# TTGO_shield_revD.net
KiCad netlist of a schematic drawn in EAGLE
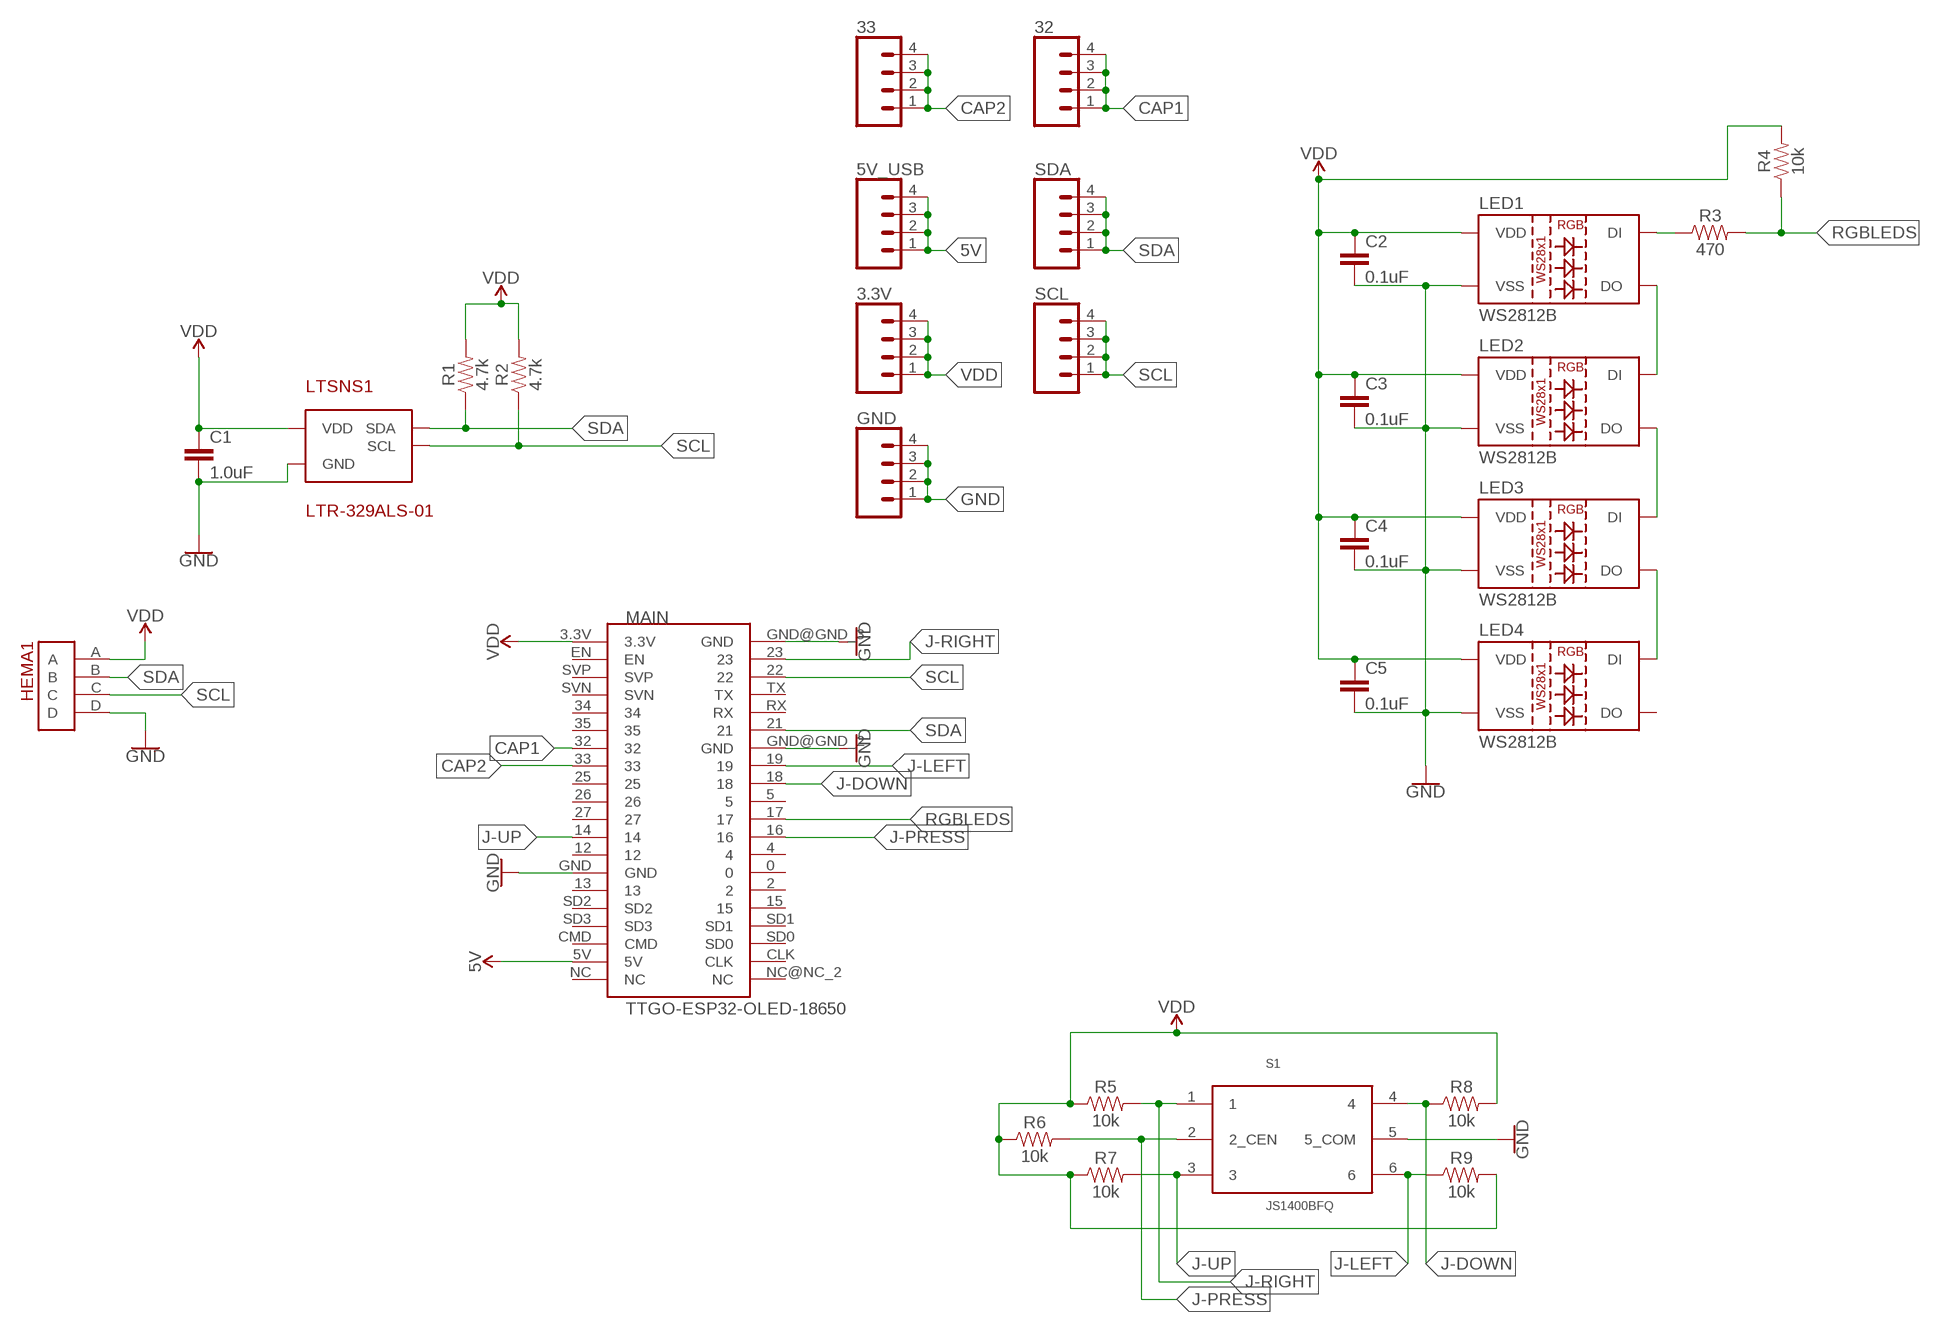
[diagram p0: schematic, sheet 1]

(export (version "E")
  (design (tool "Eeschema 10.0.6"))
  (components
    (comp (ref "3.3V")
      (value "CONN_041X04_NO_SILK")
      (footprint "eagle-import:1X04_NO_SILK")
      (libsource (lib "eagle-import") (part "CONN_041X04_NO_SILK"))
    )
    (comp (ref "5V_USB")
      (value "CONN_041X04_NO_SILK")
      (footprint "eagle-import:1X04_NO_SILK")
      (libsource (lib "eagle-import") (part "CONN_041X04_NO_SILK"))
    )
    (comp (ref "32")
      (value "CONN_041X04_NO_SILK")
      (footprint "eagle-import:1X04_NO_SILK")
      (libsource (lib "eagle-import") (part "CONN_041X04_NO_SILK"))
    )
    (comp (ref "33")
      (value "CONN_041X04_NO_SILK")
      (footprint "eagle-import:1X04_NO_SILK")
      (libsource (lib "eagle-import") (part "CONN_041X04_NO_SILK"))
    )
    (comp (ref "C1")
      (value "1.0uF")
      (footprint "eagle-import:0805")
      (libsource (lib "eagle-import") (part "1.0UF-0805-25V-10%"))
    )
    (comp (ref "C2")
      (value "0.1uF")
      (footprint "eagle-import:0603")
      (libsource (lib "eagle-import") (part "0.1UF-0603-25V-5%"))
    )
    (comp (ref "C3")
      (value "0.1uF")
      (footprint "eagle-import:0603")
      (libsource (lib "eagle-import") (part "0.1UF-0603-25V-5%"))
    )
    (comp (ref "C4")
      (value "0.1uF")
      (footprint "eagle-import:0603")
      (libsource (lib "eagle-import") (part "0.1UF-0603-25V-5%"))
    )
    (comp (ref "C5")
      (value "0.1uF")
      (footprint "eagle-import:0603")
      (libsource (lib "eagle-import") (part "0.1UF-0603-25V-5%"))
    )
    (comp (ref "GND")
      (value "CONN_041X04_NO_SILK")
      (footprint "eagle-import:1X04_NO_SILK")
      (libsource (lib "eagle-import") (part "CONN_041X04_NO_SILK"))
    )
    (comp (ref "HEMA1")
      (value "10120045-400LF")
      (footprint "eagle-import:10120045-400LF")
      (libsource (lib "eagle-import") (part "10120045-400LF"))
    )
    (comp (ref "LED1")
      (value "WS2812B")
      (footprint "eagle-import:WS2812B")
      (libsource (lib "eagle-import") (part "WS2812B"))
    )
    (comp (ref "LED2")
      (value "WS2812B")
      (footprint "eagle-import:WS2812B")
      (libsource (lib "eagle-import") (part "WS2812B"))
    )
    (comp (ref "LED3")
      (value "WS2812B")
      (footprint "eagle-import:WS2812B")
      (libsource (lib "eagle-import") (part "WS2812B"))
    )
    (comp (ref "LED4")
      (value "WS2812B")
      (footprint "eagle-import:WS2812B")
      (libsource (lib "eagle-import") (part "WS2812B"))
    )
    (comp (ref "LTSNS1")
      (value "LTR-329ALS-01")
      (footprint "eagle-import:CHIPLED-4")
      (libsource (lib "eagle-import") (part "LTR-329ALS-01"))
    )
    (comp (ref "MAIN")
      (value "TTGO-ESP32-OLED-18650")
      (footprint "eagle-import:TTGO-ESP32-OLED-18650")
      (libsource (lib "eagle-import") (part "TTGO-ESP32-OLED-18650"))
    )
    (comp (ref "R1")
      (value "4.7k")
      (footprint "eagle-import:0603")
      (libsource (lib "eagle-import") (part "4.7KOHM-0603-1/10W-1%"))
    )
    (comp (ref "R2")
      (value "4.7k")
      (footprint "eagle-import:0603")
      (libsource (lib "eagle-import") (part "4.7KOHM-0603-1/10W-1%"))
    )
    (comp (ref "R3")
      (value "470")
      (footprint "eagle-import:0603")
      (libsource (lib "eagle-import") (part "470OHM-0603-1/10W-1%"))
    )
    (comp (ref "R4")
      (value "10k")
      (footprint "eagle-import:0603")
      (libsource (lib "eagle-import") (part "10KOHM-0603-1/10W-1%"))
    )
    (comp (ref "R5")
      (value "10k")
      (footprint "eagle-import:0603")
      (libsource (lib "eagle-import") (part "10KOHM-0603-1/10W-1%"))
    )
    (comp (ref "R6")
      (value "10k")
      (footprint "eagle-import:0603")
      (libsource (lib "eagle-import") (part "10KOHM-0603-1/10W-1%"))
    )
    (comp (ref "R7")
      (value "10k")
      (footprint "eagle-import:0603")
      (libsource (lib "eagle-import") (part "10KOHM-0603-1/10W-1%"))
    )
    (comp (ref "R8")
      (value "10k")
      (footprint "eagle-import:0603")
      (libsource (lib "eagle-import") (part "10KOHM-0603-1/10W-1%"))
    )
    (comp (ref "R9")
      (value "10k")
      (footprint "eagle-import:0603")
      (libsource (lib "eagle-import") (part "10KOHM-0603-1/10W-1%"))
    )
    (comp (ref "S1")
      (value "JS1400BFQ")
      (footprint "eagle-import:JS1400BFQ")
      (libsource (lib "eagle-import") (part "JS1400BFQ"))
    )
    (comp (ref "SCL")
      (value "CONN_041X04_NO_SILK")
      (footprint "eagle-import:1X04_NO_SILK")
      (libsource (lib "eagle-import") (part "CONN_041X04_NO_SILK"))
    )
    (comp (ref "SDA")
      (value "CONN_041X04_NO_SILK")
      (footprint "eagle-import:1X04_NO_SILK")
      (libsource (lib "eagle-import") (part "CONN_041X04_NO_SILK"))
    )
  )
  (nets
    (net (code "1") (name "5V") (class "Default")
      (node (ref "5V_USB") (pin "1") (pinfunction "1_1") (pintype "passive"))
      (node (ref "5V_USB") (pin "2") (pinfunction "2_2") (pintype "passive"))
      (node (ref "5V_USB") (pin "3") (pinfunction "3_3") (pintype "passive"))
      (node (ref "5V_USB") (pin "4") (pinfunction "4_4") (pintype "passive"))
      (node (ref "MAIN") (pin "5V") (pinfunction "5V_5V") (pintype "bidirectional"))
    )
    (net (code "2") (name "CAP1") (class "Default")
      (node (ref "32") (pin "1") (pinfunction "1_1") (pintype "passive"))
      (node (ref "32") (pin "2") (pinfunction "2_2") (pintype "passive"))
      (node (ref "32") (pin "3") (pinfunction "3_3") (pintype "passive"))
      (node (ref "32") (pin "4") (pinfunction "4_4") (pintype "passive"))
      (node (ref "MAIN") (pin "32") (pinfunction "32_32") (pintype "bidirectional"))
    )
    (net (code "3") (name "CAP2") (class "Default")
      (node (ref "33") (pin "1") (pinfunction "1_1") (pintype "passive"))
      (node (ref "33") (pin "2") (pinfunction "2_2") (pintype "passive"))
      (node (ref "33") (pin "3") (pinfunction "3_3") (pintype "passive"))
      (node (ref "33") (pin "4") (pinfunction "4_4") (pintype "passive"))
      (node (ref "MAIN") (pin "33") (pinfunction "33_33") (pintype "bidirectional"))
    )
    (net (code "4") (name "GND") (class "Default")
      (node (ref "C1") (pin "2") (pinfunction "2_2") (pintype "passive"))
      (node (ref "C2") (pin "2") (pinfunction "2_2") (pintype "passive"))
      (node (ref "C3") (pin "2") (pinfunction "2_2") (pintype "passive"))
      (node (ref "C4") (pin "2") (pinfunction "2_2") (pintype "passive"))
      (node (ref "C5") (pin "2") (pinfunction "2_2") (pintype "passive"))
      (node (ref "GND") (pin "1") (pinfunction "1_1") (pintype "passive"))
      (node (ref "GND") (pin "2") (pinfunction "2_2") (pintype "passive"))
      (node (ref "GND") (pin "3") (pinfunction "3_3") (pintype "passive"))
      (node (ref "GND") (pin "4") (pinfunction "4_4") (pintype "passive"))
      (node (ref "HEMA1") (pin "D") (pinfunction "D_D") (pintype "bidirectional"))
      (node (ref "LED1") (pin "3") (pinfunction "VSS_3") (pintype "bidirectional"))
      (node (ref "LED2") (pin "3") (pinfunction "VSS_3") (pintype "bidirectional"))
      (node (ref "LED3") (pin "3") (pinfunction "VSS_3") (pintype "bidirectional"))
      (node (ref "LED4") (pin "3") (pinfunction "VSS_3") (pintype "bidirectional"))
      (node (ref "LTSNS1") (pin "2") (pinfunction "GND_2") (pintype "bidirectional"))
      (node (ref "MAIN") (pin "GND") (pinfunction "GND_GND") (pintype "bidirectional"))
      (node (ref "MAIN") (pin "GND@GND_2") (pinfunction "GND_GND@GND_2") (pintype "bidirectional"))
      (node (ref "MAIN") (pin "GND@GND_3") (pinfunction "GND_GND@GND_3") (pintype "bidirectional"))
      (node (ref "S1") (pin "5") (pinfunction "5_COM_5") (pintype "bidirectional"))
    )
    (net (code "5") (name "J-DOWN") (class "Default")
      (node (ref "MAIN") (pin "18") (pinfunction "18_18") (pintype "bidirectional"))
      (node (ref "R8") (pin "1") (pinfunction "1_1") (pintype "passive"))
      (node (ref "S1") (pin "4") (pinfunction "4_4") (pintype "bidirectional"))
    )
    (net (code "6") (name "J-LEFT") (class "Default")
      (node (ref "MAIN") (pin "19") (pinfunction "19_19") (pintype "bidirectional"))
      (node (ref "R9") (pin "1") (pinfunction "1_1") (pintype "passive"))
      (node (ref "S1") (pin "6") (pinfunction "6_6") (pintype "bidirectional"))
    )
    (net (code "7") (name "J-PRESS") (class "Default")
      (node (ref "MAIN") (pin "16") (pinfunction "16_16") (pintype "bidirectional"))
      (node (ref "R6") (pin "2") (pinfunction "2_2") (pintype "passive"))
      (node (ref "S1") (pin "2") (pinfunction "2_CEN_2") (pintype "bidirectional"))
    )
    (net (code "8") (name "J-RIGHT") (class "Default")
      (node (ref "MAIN") (pin "23") (pinfunction "23_23") (pintype "bidirectional"))
      (node (ref "R5") (pin "2") (pinfunction "2_2") (pintype "passive"))
      (node (ref "S1") (pin "1") (pinfunction "1_1") (pintype "bidirectional"))
    )
    (net (code "9") (name "J-UP") (class "Default")
      (node (ref "MAIN") (pin "14") (pinfunction "14_14") (pintype "bidirectional"))
      (node (ref "R7") (pin "2") (pinfunction "2_2") (pintype "passive"))
      (node (ref "S1") (pin "3") (pinfunction "3_3") (pintype "bidirectional"))
    )
    (net (code "10") (name "Net-(LED1-DI)") (class "Default")
      (node (ref "LED1") (pin "4") (pinfunction "DI_4") (pintype "bidirectional"))
      (node (ref "R3") (pin "1") (pinfunction "1_1") (pintype "passive"))
    )
    (net (code "11") (name "Net-(LED1-DO)") (class "Default")
      (node (ref "LED1") (pin "2") (pinfunction "DO_2") (pintype "bidirectional"))
      (node (ref "LED2") (pin "4") (pinfunction "DI_4") (pintype "bidirectional"))
    )
    (net (code "12") (name "Net-(LED2-DO)") (class "Default")
      (node (ref "LED2") (pin "2") (pinfunction "DO_2") (pintype "bidirectional"))
      (node (ref "LED3") (pin "4") (pinfunction "DI_4") (pintype "bidirectional"))
    )
    (net (code "13") (name "Net-(LED3-DO)") (class "Default")
      (node (ref "LED3") (pin "2") (pinfunction "DO_2") (pintype "bidirectional"))
      (node (ref "LED4") (pin "4") (pinfunction "DI_4") (pintype "bidirectional"))
    )
    (net (code "14") (name "RGBLEDS") (class "Default")
      (node (ref "MAIN") (pin "17") (pinfunction "17_17") (pintype "bidirectional"))
      (node (ref "R3") (pin "2") (pinfunction "2_2") (pintype "passive"))
      (node (ref "R4") (pin "1") (pinfunction "1_1") (pintype "passive"))
    )
    (net (code "15") (name "SCL") (class "Default")
      (node (ref "HEMA1") (pin "C") (pinfunction "C_C") (pintype "bidirectional"))
      (node (ref "LTSNS1") (pin "4") (pinfunction "SCL_4") (pintype "bidirectional"))
      (node (ref "MAIN") (pin "22") (pinfunction "22_22") (pintype "bidirectional"))
      (node (ref "R2") (pin "1") (pinfunction "1_1") (pintype "passive"))
      (node (ref "SCL") (pin "1") (pinfunction "1_1") (pintype "passive"))
      (node (ref "SCL") (pin "2") (pinfunction "2_2") (pintype "passive"))
      (node (ref "SCL") (pin "3") (pinfunction "3_3") (pintype "passive"))
      (node (ref "SCL") (pin "4") (pinfunction "4_4") (pintype "passive"))
    )
    (net (code "16") (name "SDA") (class "Default")
      (node (ref "HEMA1") (pin "B") (pinfunction "B_B") (pintype "bidirectional"))
      (node (ref "LTSNS1") (pin "3") (pinfunction "SDA_3") (pintype "bidirectional"))
      (node (ref "MAIN") (pin "21") (pinfunction "21_21") (pintype "bidirectional"))
      (node (ref "R1") (pin "1") (pinfunction "1_1") (pintype "passive"))
      (node (ref "SDA") (pin "1") (pinfunction "1_1") (pintype "passive"))
      (node (ref "SDA") (pin "2") (pinfunction "2_2") (pintype "passive"))
      (node (ref "SDA") (pin "3") (pinfunction "3_3") (pintype "passive"))
      (node (ref "SDA") (pin "4") (pinfunction "4_4") (pintype "passive"))
    )
    (net (code "17") (name "VDD") (class "Default")
      (node (ref "3.3V") (pin "1") (pinfunction "1_1") (pintype "passive"))
      (node (ref "3.3V") (pin "2") (pinfunction "2_2") (pintype "passive"))
      (node (ref "3.3V") (pin "3") (pinfunction "3_3") (pintype "passive"))
      (node (ref "3.3V") (pin "4") (pinfunction "4_4") (pintype "passive"))
      (node (ref "C1") (pin "1") (pinfunction "1_1") (pintype "passive"))
      (node (ref "C2") (pin "1") (pinfunction "1_1") (pintype "passive"))
      (node (ref "C3") (pin "1") (pinfunction "1_1") (pintype "passive"))
      (node (ref "C4") (pin "1") (pinfunction "1_1") (pintype "passive"))
      (node (ref "C5") (pin "1") (pinfunction "1_1") (pintype "passive"))
      (node (ref "HEMA1") (pin "A") (pinfunction "A_A") (pintype "bidirectional"))
      (node (ref "LED1") (pin "1") (pinfunction "VDD_1") (pintype "bidirectional"))
      (node (ref "LED2") (pin "1") (pinfunction "VDD_1") (pintype "bidirectional"))
      (node (ref "LED3") (pin "1") (pinfunction "VDD_1") (pintype "bidirectional"))
      (node (ref "LED4") (pin "1") (pinfunction "VDD_1") (pintype "bidirectional"))
      (node (ref "LTSNS1") (pin "1") (pinfunction "VDD_1") (pintype "bidirectional"))
      (node (ref "MAIN") (pin "3.3V") (pinfunction "3.3V_3.3V") (pintype "bidirectional"))
      (node (ref "R1") (pin "2") (pinfunction "2_2") (pintype "passive"))
      (node (ref "R2") (pin "2") (pinfunction "2_2") (pintype "passive"))
      (node (ref "R4") (pin "2") (pinfunction "2_2") (pintype "passive"))
      (node (ref "R5") (pin "1") (pinfunction "1_1") (pintype "passive"))
      (node (ref "R6") (pin "1") (pinfunction "1_1") (pintype "passive"))
      (node (ref "R7") (pin "1") (pinfunction "1_1") (pintype "passive"))
      (node (ref "R8") (pin "2") (pinfunction "2_2") (pintype "passive"))
      (node (ref "R9") (pin "2") (pinfunction "2_2") (pintype "passive"))
    )
    (net (code "18") (name "unconnected-(LED4-DO-Pad2)") (class "Default")
      (node (ref "LED4") (pin "2") (pinfunction "DO_2") (pintype "bidirectional"))
    )
    (net (code "19") (name "unconnected-(MAIN-NC-PadNC@NC_2)") (class "Default")
      (node (ref "MAIN") (pin "NC@NC_2") (pinfunction "NC_NC@NC_2") (pintype "bidirectional"))
    )
    (net (code "20") (name "unconnected-(MAIN-Pad0)") (class "Default")
      (node (ref "MAIN") (pin "0") (pinfunction "0_0") (pintype "bidirectional"))
    )
    (net (code "21") (name "unconnected-(MAIN-Pad2)") (class "Default")
      (node (ref "MAIN") (pin "2") (pinfunction "2_2") (pintype "bidirectional"))
    )
    (net (code "22") (name "unconnected-(MAIN-Pad4)") (class "Default")
      (node (ref "MAIN") (pin "4") (pinfunction "4_4") (pintype "bidirectional"))
    )
    (net (code "23") (name "unconnected-(MAIN-Pad5)") (class "Default")
      (node (ref "MAIN") (pin "5") (pinfunction "5_5") (pintype "bidirectional"))
    )
    (net (code "24") (name "unconnected-(MAIN-Pad12)") (class "Default")
      (node (ref "MAIN") (pin "12") (pinfunction "12_12") (pintype "bidirectional"))
    )
    (net (code "25") (name "unconnected-(MAIN-Pad13)") (class "Default")
      (node (ref "MAIN") (pin "13") (pinfunction "13_13") (pintype "bidirectional"))
    )
    (net (code "26") (name "unconnected-(MAIN-Pad15)") (class "Default")
      (node (ref "MAIN") (pin "15") (pinfunction "15_15") (pintype "bidirectional"))
    )
    (net (code "27") (name "unconnected-(MAIN-Pad25)") (class "Default")
      (node (ref "MAIN") (pin "25") (pinfunction "25_25") (pintype "bidirectional"))
    )
    (net (code "28") (name "unconnected-(MAIN-Pad26)") (class "Default")
      (node (ref "MAIN") (pin "26") (pinfunction "26_26") (pintype "bidirectional"))
    )
    (net (code "29") (name "unconnected-(MAIN-Pad27)") (class "Default")
      (node (ref "MAIN") (pin "27") (pinfunction "27_27") (pintype "bidirectional"))
    )
    (net (code "30") (name "unconnected-(MAIN-Pad34)") (class "Default")
      (node (ref "MAIN") (pin "34") (pinfunction "34_34") (pintype "bidirectional"))
    )
    (net (code "31") (name "unconnected-(MAIN-Pad35)") (class "Default")
      (node (ref "MAIN") (pin "35") (pinfunction "35_35") (pintype "bidirectional"))
    )
    (net (code "32") (name "unconnected-(MAIN-PadCLK)") (class "Default")
      (node (ref "MAIN") (pin "CLK") (pinfunction "CLK_CLK") (pintype "bidirectional"))
    )
    (net (code "33") (name "unconnected-(MAIN-PadCMD)") (class "Default")
      (node (ref "MAIN") (pin "CMD") (pinfunction "CMD_CMD") (pintype "bidirectional"))
    )
    (net (code "34") (name "unconnected-(MAIN-PadEN)") (class "Default")
      (node (ref "MAIN") (pin "EN") (pinfunction "EN_EN") (pintype "bidirectional"))
    )
    (net (code "35") (name "unconnected-(MAIN-PadNC)") (class "Default")
      (node (ref "MAIN") (pin "NC") (pinfunction "NC_NC") (pintype "bidirectional"))
    )
    (net (code "36") (name "unconnected-(MAIN-PadRX)") (class "Default")
      (node (ref "MAIN") (pin "RX") (pinfunction "RX_RX") (pintype "bidirectional"))
    )
    (net (code "37") (name "unconnected-(MAIN-PadSD0)") (class "Default")
      (node (ref "MAIN") (pin "SD0") (pinfunction "SD0_SD0") (pintype "bidirectional"))
    )
    (net (code "38") (name "unconnected-(MAIN-PadSD1)") (class "Default")
      (node (ref "MAIN") (pin "SD1") (pinfunction "SD1_SD1") (pintype "bidirectional"))
    )
    (net (code "39") (name "unconnected-(MAIN-PadSD2)") (class "Default")
      (node (ref "MAIN") (pin "SD2") (pinfunction "SD2_SD2") (pintype "bidirectional"))
    )
    (net (code "40") (name "unconnected-(MAIN-PadSD3)") (class "Default")
      (node (ref "MAIN") (pin "SD3") (pinfunction "SD3_SD3") (pintype "bidirectional"))
    )
    (net (code "41") (name "unconnected-(MAIN-PadSVN)") (class "Default")
      (node (ref "MAIN") (pin "SVN") (pinfunction "SVN_SVN") (pintype "bidirectional"))
    )
    (net (code "42") (name "unconnected-(MAIN-PadSVP)") (class "Default")
      (node (ref "MAIN") (pin "SVP") (pinfunction "SVP_SVP") (pintype "bidirectional"))
    )
    (net (code "43") (name "unconnected-(MAIN-PadTX)") (class "Default")
      (node (ref "MAIN") (pin "TX") (pinfunction "TX_TX") (pintype "bidirectional"))
    )
  )
)
